# LoadSwitch.net
KiCad netlist of a schematic drawn in EAGLE
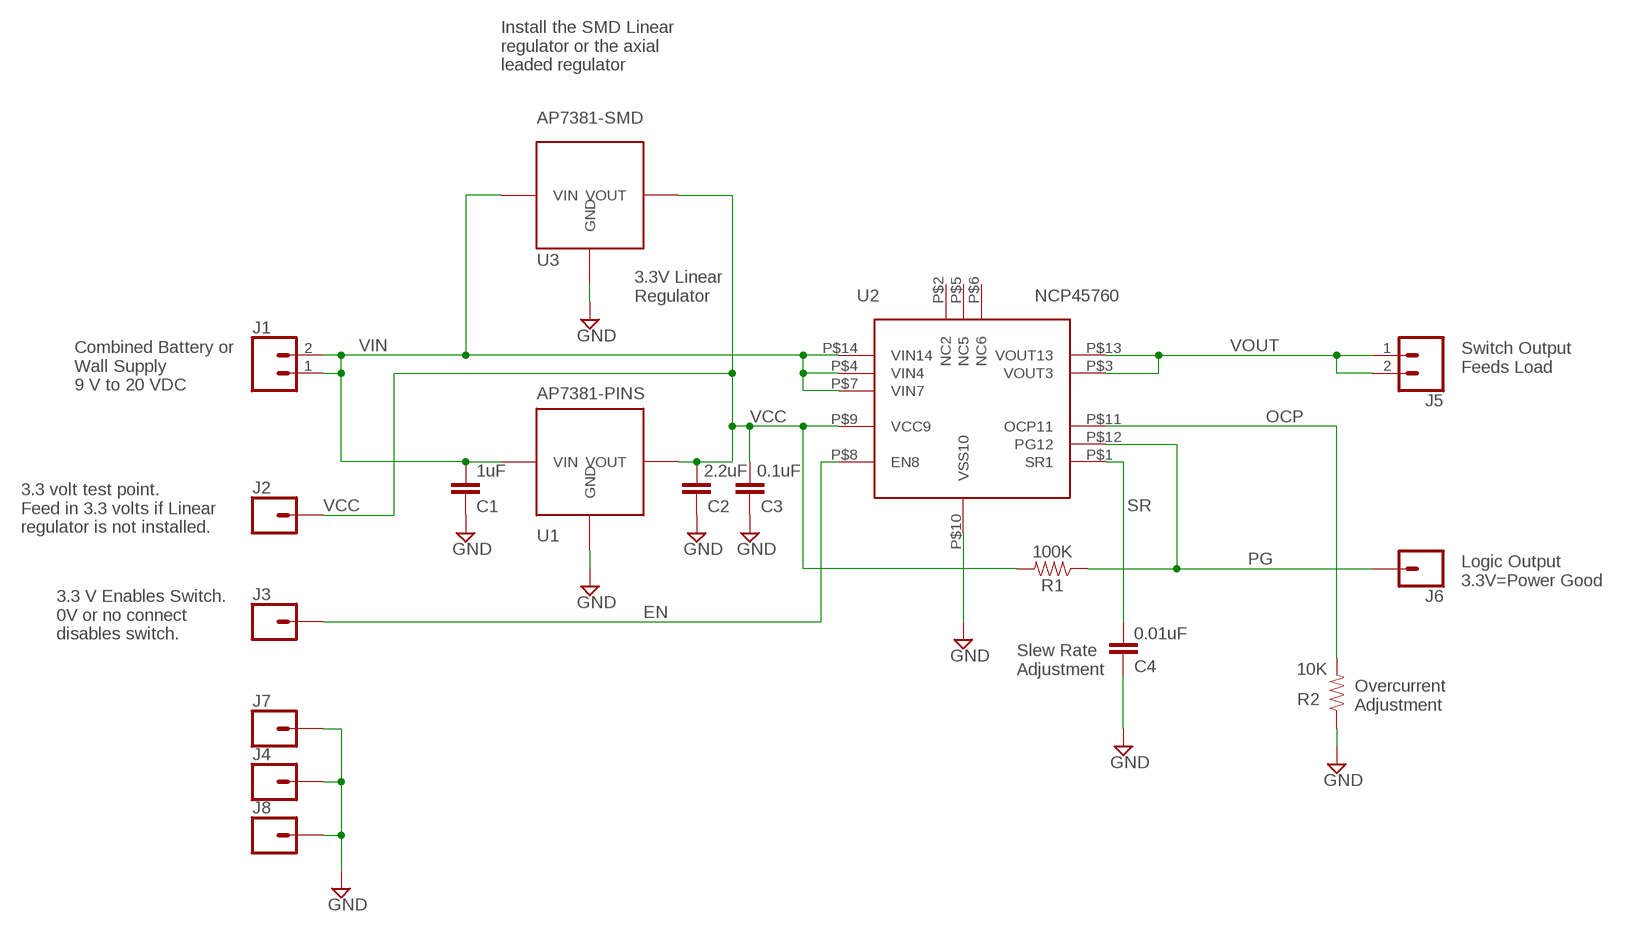
[diagram p0: schematic, sheet 1]

(export (version "E")
  (design (tool "Eeschema 10.0.6"))
  (components
    (comp (ref "C1")
      (value "1uF")
      (footprint "eagle-import:0805_CAP")
      (libsource (lib "eagle-import") (part "0805_CAP"))
    )
    (comp (ref "C2")
      (value "2.2uF")
      (footprint "eagle-import:0805_CAP")
      (libsource (lib "eagle-import") (part "0805_CAP"))
    )
    (comp (ref "C3")
      (value "0.1uF")
      (footprint "eagle-import:0805_CAP")
      (libsource (lib "eagle-import") (part "0805_CAP"))
    )
    (comp (ref "C4")
      (value "0.01uF")
      (footprint "eagle-import:0805_CAP")
      (libsource (lib "eagle-import") (part "0805_CAP"))
    )
    (comp (ref "J1")
      (value "CONN_02")
      (footprint "eagle-import:1X02")
      (libsource (lib "eagle-import") (part "CONN_02"))
    )
    (comp (ref "J2")
      (value "CONN_01")
      (footprint "eagle-import:1X01")
      (libsource (lib "eagle-import") (part "CONN_01"))
    )
    (comp (ref "J3")
      (value "CONN_01")
      (footprint "eagle-import:1X01")
      (libsource (lib "eagle-import") (part "CONN_01"))
    )
    (comp (ref "J4")
      (value "CONN_01")
      (footprint "eagle-import:1X01")
      (libsource (lib "eagle-import") (part "CONN_01"))
    )
    (comp (ref "J5")
      (value "CONN_02")
      (footprint "eagle-import:1X02")
      (libsource (lib "eagle-import") (part "CONN_02"))
    )
    (comp (ref "J6")
      (value "CONN_01")
      (footprint "eagle-import:1X01")
      (libsource (lib "eagle-import") (part "CONN_01"))
    )
    (comp (ref "J7")
      (value "CONN_01")
      (footprint "eagle-import:1X01")
      (libsource (lib "eagle-import") (part "CONN_01"))
    )
    (comp (ref "J8")
      (value "CONN_01")
      (footprint "eagle-import:1X01")
      (libsource (lib "eagle-import") (part "CONN_01"))
    )
    (comp (ref "R1")
      (value "100K")
      (footprint "eagle-import:0603_RESISTOR")
      (libsource (lib "eagle-import") (part "0603_RESISTOR"))
    )
    (comp (ref "R2")
      (value "10K")
      (footprint "eagle-import:0603_RESISTOR")
      (libsource (lib "eagle-import") (part "0603_RESISTOR"))
    )
    (comp (ref "U1")
      (value "AP7381-PINS")
      (footprint "eagle-import:AP7381_PINS")
      (libsource (lib "eagle-import") (part "AP7381_PINS"))
    )
    (comp (ref "U2")
      (value "NCP45760")
      (footprint "eagle-import:NCP45760")
      (libsource (lib "eagle-import") (part "NCP45760"))
    )
    (comp (ref "U3")
      (value "AP7381-SMD")
      (footprint "eagle-import:AP7381")
      (libsource (lib "eagle-import") (part "AP7381"))
    )
  )
  (nets
    (net (code "1") (name "/EN") (class "Default")
      (node (ref "J3") (pin "1") (pinfunction "1_1") (pintype "passive"))
      (node (ref "U2") (pin "P$8") (pinfunction "EN8_P$8") (pintype "bidirectional"))
    )
    (net (code "2") (name "/OCP") (class "Default")
      (node (ref "R2") (pin "2") (pinfunction "2_2") (pintype "passive"))
      (node (ref "U2") (pin "P$11") (pinfunction "OCP11_P$11") (pintype "bidirectional"))
    )
    (net (code "3") (name "/PG") (class "Default")
      (node (ref "J6") (pin "1") (pinfunction "1_1") (pintype "passive"))
      (node (ref "R1") (pin "1") (pinfunction "1_1") (pintype "passive"))
      (node (ref "U2") (pin "P$12") (pinfunction "PG12_P$12") (pintype "bidirectional"))
    )
    (net (code "4") (name "/SR") (class "Default")
      (node (ref "C4") (pin "1") (pinfunction "1_1") (pintype "passive"))
      (node (ref "U2") (pin "P$1") (pinfunction "SR1_P$1") (pintype "bidirectional"))
    )
    (net (code "5") (name "/VCC") (class "Default")
      (node (ref "C2") (pin "1") (pinfunction "1_1") (pintype "passive"))
      (node (ref "C3") (pin "1") (pinfunction "1_1") (pintype "passive"))
      (node (ref "J2") (pin "1") (pinfunction "1_1") (pintype "passive"))
      (node (ref "R1") (pin "2") (pinfunction "2_2") (pintype "passive"))
      (node (ref "U1") (pin "P$1") (pinfunction "VOUT_P$1") (pintype "bidirectional"))
      (node (ref "U2") (pin "P$9") (pinfunction "VCC9_P$9") (pintype "bidirectional"))
      (node (ref "U3") (pin "P$1") (pinfunction "VOUT_P$1") (pintype "bidirectional"))
    )
    (net (code "6") (name "/VIN") (class "Default")
      (node (ref "C1") (pin "1") (pinfunction "1_1") (pintype "passive"))
      (node (ref "J1") (pin "1") (pinfunction "1_1") (pintype "passive"))
      (node (ref "J1") (pin "2") (pinfunction "2_2") (pintype "passive"))
      (node (ref "U1") (pin "P$3") (pinfunction "VIN_P$3") (pintype "bidirectional"))
      (node (ref "U2") (pin "P$14") (pinfunction "VIN14_P$14") (pintype "bidirectional"))
      (node (ref "U2") (pin "P$4") (pinfunction "VIN4_P$4") (pintype "bidirectional"))
      (node (ref "U2") (pin "P$7") (pinfunction "VIN7_P$7") (pintype "bidirectional"))
      (node (ref "U3") (pin "P$2") (pinfunction "VIN_P$2") (pintype "bidirectional"))
    )
    (net (code "7") (name "/VOUT") (class "Default")
      (node (ref "J5") (pin "1") (pinfunction "1_1") (pintype "passive"))
      (node (ref "J5") (pin "2") (pinfunction "2_2") (pintype "passive"))
      (node (ref "U2") (pin "P$13") (pinfunction "VOUT13_P$13") (pintype "bidirectional"))
      (node (ref "U2") (pin "P$3") (pinfunction "VOUT3_P$3") (pintype "bidirectional"))
    )
    (net (code "8") (name "GND") (class "Default")
      (node (ref "C1") (pin "2") (pinfunction "2_2") (pintype "passive"))
      (node (ref "C2") (pin "2") (pinfunction "2_2") (pintype "passive"))
      (node (ref "C3") (pin "2") (pinfunction "2_2") (pintype "passive"))
      (node (ref "C4") (pin "2") (pinfunction "2_2") (pintype "passive"))
      (node (ref "J4") (pin "1") (pinfunction "1_1") (pintype "passive"))
      (node (ref "J7") (pin "1") (pinfunction "1_1") (pintype "passive"))
      (node (ref "J8") (pin "1") (pinfunction "1_1") (pintype "passive"))
      (node (ref "R2") (pin "1") (pinfunction "1_1") (pintype "passive"))
      (node (ref "U1") (pin "P$2") (pinfunction "GND_P$2") (pintype "bidirectional"))
      (node (ref "U2") (pin "P$10") (pinfunction "VSS10_P$10") (pintype "bidirectional"))
      (node (ref "U3") (pin "P$3") (pinfunction "GND_P$3") (pintype "bidirectional"))
      (node (ref "U3") (pin "P$4") (pinfunction "GND_P$4") (pintype "bidirectional"))
    )
    (net (code "9") (name "unconnected-(U2-NC2-PadP$2)") (class "Default")
      (node (ref "U2") (pin "P$2") (pinfunction "NC2_P$2") (pintype "bidirectional"))
    )
    (net (code "10") (name "unconnected-(U2-NC5-PadP$5)") (class "Default")
      (node (ref "U2") (pin "P$5") (pinfunction "NC5_P$5") (pintype "bidirectional"))
    )
    (net (code "11") (name "unconnected-(U2-NC6-PadP$6)") (class "Default")
      (node (ref "U2") (pin "P$6") (pinfunction "NC6_P$6") (pintype "bidirectional"))
    )
  )
)
